# DetectorBoard_V100_DET.net
KiCad netlist of a schematic drawn in Altium Designer
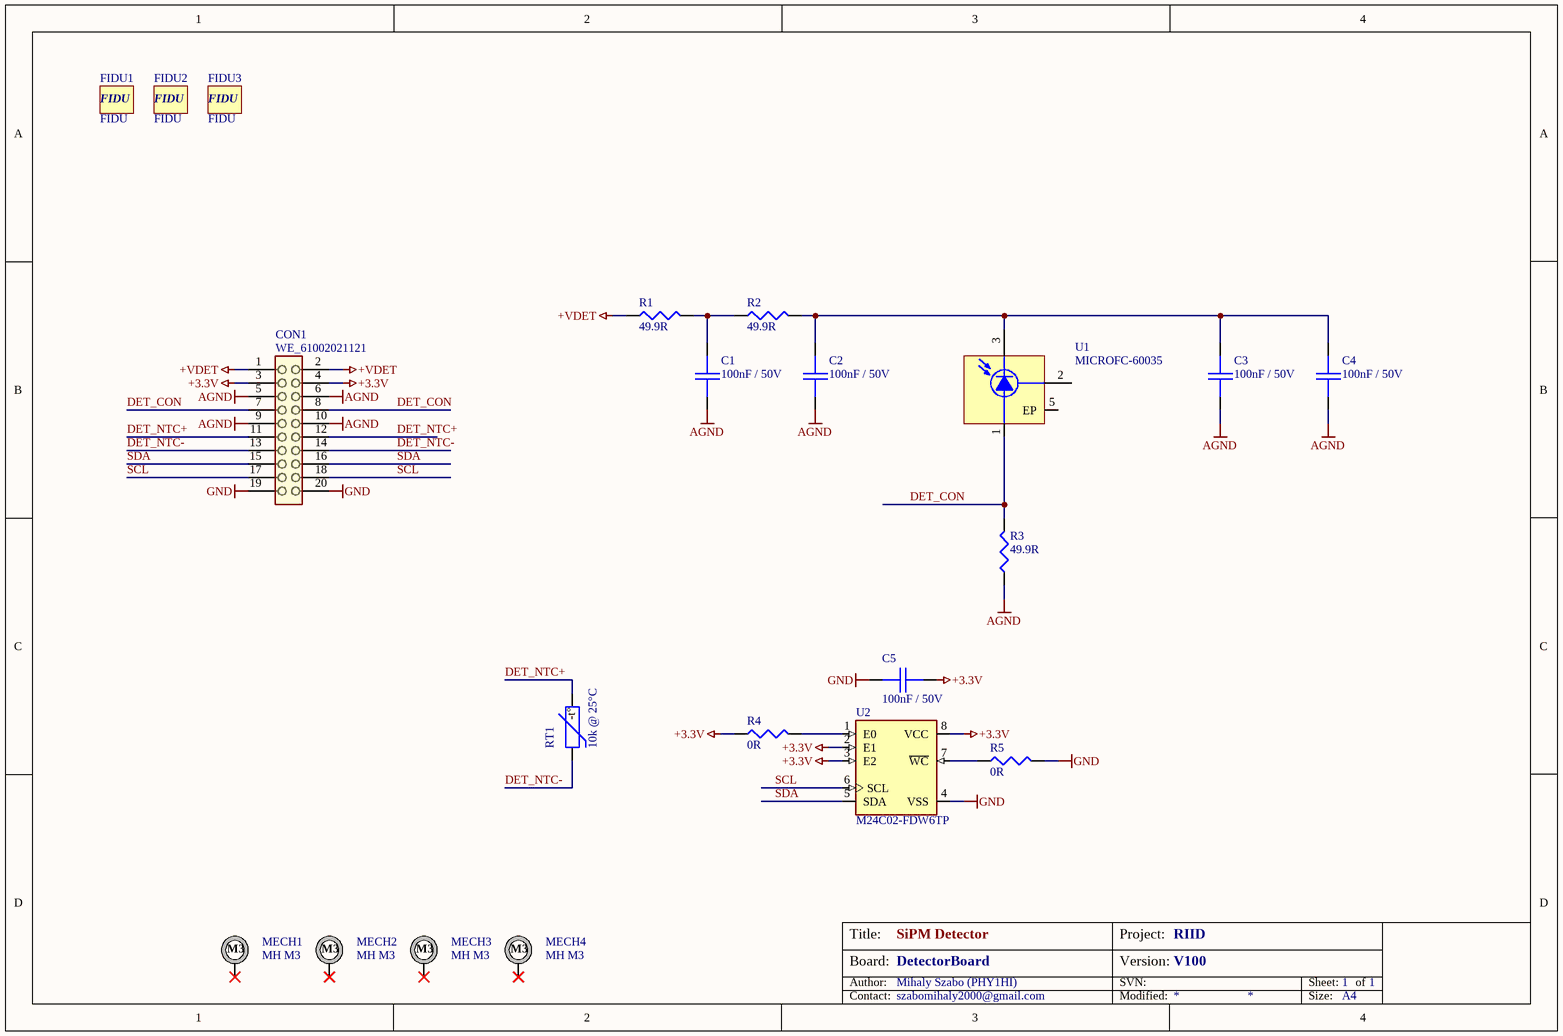
[diagram p0: DetectorBoard_V100_DET.SchDoc]

(export (version "E")
  (design (tool "Eeschema 10.0.6"))
  (components
    (comp (ref "C1")
      (value "100nF / 50V")
      (footprint "0805_C")
      (description "100nF 50V X7R")
      (fields (field (name "PART NUMBER") "SMD0805-100nF-50V"))
      (libsource (lib "ALTIUM_DB_LIB") (part "CAP_NONPOL"))
    )
    (comp (ref "C2")
      (value "100nF / 50V")
      (footprint "0805_C")
      (description "100nF 50V X7R")
      (fields (field (name "PART NUMBER") "SMD0805-100nF-50V"))
      (libsource (lib "ALTIUM_DB_LIB") (part "CAP_NONPOL"))
    )
    (comp (ref "C3")
      (value "100nF / 50V")
      (footprint "0805_C")
      (description "100nF 50V X7R")
      (fields (field (name "PART NUMBER") "SMD0805-100nF-50V"))
      (libsource (lib "ALTIUM_DB_LIB") (part "CAP_NONPOL"))
    )
    (comp (ref "C4")
      (value "100nF / 50V")
      (footprint "0805_C")
      (description "100nF 50V X7R")
      (fields (field (name "PART NUMBER") "SMD0805-100nF-50V"))
      (libsource (lib "ALTIUM_DB_LIB") (part "CAP_NONPOL"))
    )
    (comp (ref "C5")
      (value "100nF / 50V")
      (footprint "0805_C")
      (description "100nF 50V X7R")
      (fields (field (name "PART NUMBER") "SMD0805-100nF-50V"))
      (libsource (lib "ALTIUM_DB_LIB") (part "CAP_NONPOL"))
    )
    (comp (ref "CON1")
      (value "WE_61002021121")
      (footprint "WE_61002021121")
      (description "Board-To-Board Connector, Vertical, 2.54 mm, 2x10 Contacts, Header, WR-PHD Series, SMD")
      (fields (field (name "PART NUMBER") "61002021121"))
      (libsource (lib "ALTIUM_DB_LIB") (part "CON20 (2 x 10)"))
    )
    (comp (ref "FIDU1")
      (value "FIDU")
      (footprint "FIDU_4x4")
      (description "FIDU, 4x4mm, rectangle")
      (fields (field (name "PART NUMBER") "FIDU_4x4"))
      (libsource (lib "ALTIUM_DB_LIB") (part "FIDU"))
    )
    (comp (ref "FIDU2")
      (value "FIDU")
      (footprint "FIDU_4x4")
      (description "FIDU, 4x4mm, rectangle")
      (fields (field (name "PART NUMBER") "FIDU_4x4"))
      (libsource (lib "ALTIUM_DB_LIB") (part "FIDU"))
    )
    (comp (ref "FIDU3")
      (value "FIDU")
      (footprint "FIDU_4x4")
      (description "FIDU, 4x4mm, rectangle")
      (fields (field (name "PART NUMBER") "FIDU_4x4"))
      (libsource (lib "ALTIUM_DB_LIB") (part "FIDU"))
    )
    (comp (ref "MECH1")
      (value "MH M3")
      (footprint "PAD_M3 x 7")
      (description "3.2/7mm Mounting_Hole_M3")
      (fields (field (name "PART NUMBER") "Mounting_Hole_M3"))
      (libsource (lib "ALTIUM_DB_LIB") (part "Mounting_Hole_M3"))
    )
    (comp (ref "MECH2")
      (value "MH M3")
      (footprint "PAD_M3 x 7")
      (description "3.2/7mm Mounting_Hole_M3")
      (fields (field (name "PART NUMBER") "Mounting_Hole_M3"))
      (libsource (lib "ALTIUM_DB_LIB") (part "Mounting_Hole_M3"))
    )
    (comp (ref "MECH3")
      (value "MH M3")
      (footprint "PAD_M3 x 7")
      (description "3.2/7mm Mounting_Hole_M3")
      (fields (field (name "PART NUMBER") "Mounting_Hole_M3"))
      (libsource (lib "ALTIUM_DB_LIB") (part "Mounting_Hole_M3"))
    )
    (comp (ref "MECH4")
      (value "MH M3")
      (footprint "PAD_M3 x 7")
      (description "3.2/7mm Mounting_Hole_M3")
      (fields (field (name "PART NUMBER") "Mounting_Hole_M3"))
      (libsource (lib "ALTIUM_DB_LIB") (part "Mounting_Hole_M3"))
    )
    (comp (ref "R1")
      (value "49.9R")
      (footprint "0805")
      (description "49.9R 0805 0.125W 1%")
      (fields (field (name "PART NUMBER") "SMD0805-49.9R 1%"))
      (libsource (lib "ALTIUM_DB_LIB") (part "RESISTOR"))
    )
    (comp (ref "R2")
      (value "49.9R")
      (footprint "0805")
      (description "49.9R 0805 0.125W 1%")
      (fields (field (name "PART NUMBER") "SMD0805-49.9R 1%"))
      (libsource (lib "ALTIUM_DB_LIB") (part "RESISTOR"))
    )
    (comp (ref "R3")
      (value "49.9R")
      (footprint "0805")
      (description "49.9R 0805 0.125W 1%")
      (fields (field (name "PART NUMBER") "SMD0805-49.9R 1%"))
      (libsource (lib "ALTIUM_DB_LIB") (part "RESISTOR"))
    )
    (comp (ref "R4")
      (value "0R")
      (footprint "0805")
      (description "0R 0805 0.125W 5%")
      (fields (field (name "PART NUMBER") "0 R 5%"))
      (libsource (lib "ALTIUM_DB_LIB") (part "RESISTOR"))
    )
    (comp (ref "R5")
      (value "0R")
      (footprint "0805")
      (description "0R 0805 0.125W 5%")
      (fields (field (name "PART NUMBER") "0 R 5%"))
      (libsource (lib "ALTIUM_DB_LIB") (part "RESISTOR"))
    )
    (comp (ref "RT1")
      (value "10k @ 25°C")
      (footprint "0805")
      (description "NTC (Negative Temperature Coefficient) Thermistors THERMISTOR 0805 10K/3435")
      (fields (field (name "PART NUMBER") "TX08F103F3435ER"))
      (libsource (lib "ALTIUM_DB_LIB") (part "NTC_GENERAL"))
    )
    (comp (ref "U1")
      (value "MICROFC-60035")
      (footprint "MICROFC-60035-SMT-TR")
      (description "Silicon Photomultipliers(SiPM), Low-Noise,Blue-Sensitive")
      (fields (field (name "MF") "ON Semiconductor") (field (name "MP") "MICROFC-60035-SMT-TR1"))
      (libsource (lib "ALTIUM_DB_LIB") (part "MICROFC-60035-SMT-TR1"))
    )
    (comp (ref "U2")
      (value "M24C02-FDW6TP")
      (footprint "TSSOP-8")
      (description "EEPROM Memory IC 2Kb (256 x 8) I2C 400kHz 900ns 8-TSSOP")
      (fields (field (name "MF") "STMicroelectronics") (field (name "DIGI-KEY_PART_NUMBER") "497-15746-1-ND"))
      (libsource (lib "ALTIUM_DB_LIB") (part "M24C02-FDW6TP"))
    )
  )
  (nets
    (net (code "1") (name "+3.3V") (class "Default")
      (node (ref "C5") (pin "2") (pintype "passive"))
      (node (ref "CON1") (pin "3") (pinfunction "3_3") (pintype "passive"))
      (node (ref "CON1") (pin "4") (pinfunction "4_4") (pintype "passive"))
      (node (ref "R4") (pin "1") (pintype "passive"))
      (node (ref "U2") (pin "2") (pinfunction "E1_2") (pintype "input"))
      (node (ref "U2") (pin "3") (pinfunction "E2_3") (pintype "input"))
      (node (ref "U2") (pin "8") (pinfunction "VCC_8") (pintype "power_in"))
    )
    (net (code "2") (name "+VDET") (class "Default")
      (node (ref "CON1") (pin "1") (pinfunction "1_1") (pintype "passive"))
      (node (ref "CON1") (pin "2") (pinfunction "2_2") (pintype "passive"))
      (node (ref "R1") (pin "1") (pintype "passive"))
    )
    (net (code "3") (name "/DET_CON") (class "Default")
      (node (ref "CON1") (pin "7") (pinfunction "7_7") (pintype "passive"))
      (node (ref "CON1") (pin "8") (pinfunction "8_8") (pintype "passive"))
      (node (ref "R3") (pin "2") (pintype "passive"))
      (node (ref "U1") (pin "1") (pinfunction "P-ANODE_1") (pintype "passive"))
    )
    (net (code "4") (name "/DET_NTC+") (class "Default")
      (node (ref "CON1") (pin "11") (pinfunction "11_11") (pintype "passive"))
      (node (ref "CON1") (pin "12") (pinfunction "12_12") (pintype "passive"))
      (node (ref "RT1") (pin "2") (pintype "passive"))
    )
    (net (code "5") (name "/DET_NTC-") (class "Default")
      (node (ref "CON1") (pin "13") (pinfunction "13_13") (pintype "passive"))
      (node (ref "CON1") (pin "14") (pinfunction "14_14") (pintype "passive"))
      (node (ref "RT1") (pin "1") (pintype "passive"))
    )
    (net (code "6") (name "/SCL") (class "Default")
      (node (ref "CON1") (pin "17") (pinfunction "17_17") (pintype "passive"))
      (node (ref "CON1") (pin "18") (pinfunction "18_18") (pintype "passive"))
      (node (ref "U2") (pin "6") (pinfunction "SCL_6") (pintype "input"))
    )
    (net (code "7") (name "/SDA") (class "Default")
      (node (ref "CON1") (pin "15") (pinfunction "15_15") (pintype "passive"))
      (node (ref "CON1") (pin "16") (pinfunction "16_16") (pintype "passive"))
      (node (ref "U2") (pin "5") (pinfunction "SDA_5") (pintype "bidirectional"))
    )
    (net (code "8") (name "AGND") (class "Default")
      (node (ref "C1") (pin "2") (pintype "passive"))
      (node (ref "C2") (pin "2") (pintype "passive"))
      (node (ref "C3") (pin "2") (pintype "passive"))
      (node (ref "C4") (pin "2") (pintype "passive"))
      (node (ref "CON1") (pin "10") (pinfunction "10_10") (pintype "passive"))
      (node (ref "CON1") (pin "5") (pinfunction "5_5") (pintype "passive"))
      (node (ref "CON1") (pin "6") (pinfunction "6_6") (pintype "passive"))
      (node (ref "CON1") (pin "9") (pinfunction "9_9") (pintype "passive"))
      (node (ref "R3") (pin "1") (pintype "passive"))
    )
    (net (code "9") (name "GND") (class "Default")
      (node (ref "C5") (pin "1") (pintype "passive"))
      (node (ref "CON1") (pin "19") (pinfunction "19_19") (pintype "passive"))
      (node (ref "CON1") (pin "20") (pinfunction "20_20") (pintype "passive"))
      (node (ref "R5") (pin "2") (pintype "passive"))
      (node (ref "U2") (pin "4") (pinfunction "VSS_4") (pintype "power_in"))
    )
    (net (code "10") (name "Net-(C1-Pad1)") (class "Default")
      (node (ref "C1") (pin "1") (pintype "passive"))
      (node (ref "R1") (pin "2") (pintype "passive"))
      (node (ref "R2") (pin "1") (pintype "passive"))
    )
    (net (code "11") (name "Net-(U1-N-CATHODE)") (class "Default")
      (node (ref "C2") (pin "1") (pintype "passive"))
      (node (ref "C3") (pin "1") (pintype "passive"))
      (node (ref "C4") (pin "1") (pintype "passive"))
      (node (ref "R2") (pin "2") (pintype "passive"))
      (node (ref "U1") (pin "3") (pinfunction "N-CATHODE_3") (pintype "passive"))
    )
    (net (code "12") (name "Net-(U2-E0)") (class "Default")
      (node (ref "R4") (pin "2") (pintype "passive"))
      (node (ref "U2") (pin "1") (pinfunction "E0_1") (pintype "input"))
    )
    (net (code "13") (name "Net-(U2-~{WC})") (class "Default")
      (node (ref "R5") (pin "1") (pintype "passive"))
      (node (ref "U2") (pin "7") (pinfunction "~{WC}_7") (pintype "input"))
    )
    (net (code "14") (name "unconnected-(MECH1-PadM3)") (class "Default")
      (node (ref "MECH1") (pin "M3") (pinfunction "M3_M3") (pintype "passive+no_connect"))
    )
    (net (code "15") (name "unconnected-(MECH2-PadM3)") (class "Default")
      (node (ref "MECH2") (pin "M3") (pinfunction "M3_M3") (pintype "passive+no_connect"))
    )
    (net (code "16") (name "unconnected-(MECH3-PadM3)") (class "Default")
      (node (ref "MECH3") (pin "M3") (pinfunction "M3_M3") (pintype "passive+no_connect"))
    )
    (net (code "17") (name "unconnected-(MECH4-PadM3)") (class "Default")
      (node (ref "MECH4") (pin "M3") (pinfunction "M3_M3") (pintype "passive+no_connect"))
    )
    (net (code "18") (name "unconnected-(U1-EP-Pad5)") (class "Default")
      (node (ref "U1") (pin "5") (pinfunction "EP_5") (pintype "power_in"))
    )
    (net (code "19") (name "unconnected-(U1-F-FAST_OUTPUT-Pad2)") (class "Default")
      (node (ref "U1") (pin "2") (pinfunction "F-FAST_OUTPUT_2") (pintype "passive"))
    )
  )
)
